# triple_filter.net
KiCad netlist of a schematic drawn in EAGLE
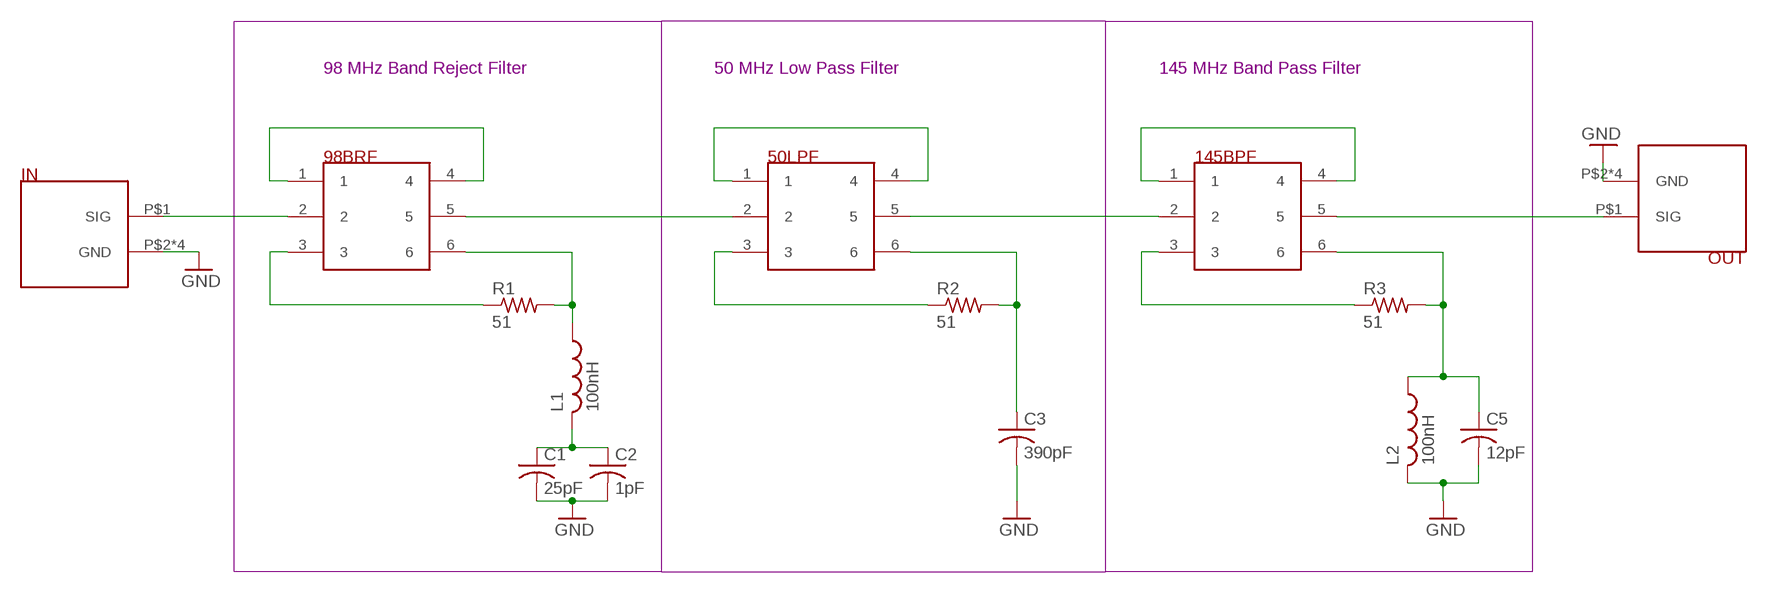
[diagram p0: schematic, sheet 1]

(export (version "E")
  (design (tool "Eeschema 10.0.6"))
  (components
    (comp (ref "50LPF")
      (value "JS202011SCQN")
      (footprint "eagle-import:JS202011SCQN")
      (libsource (lib "eagle-import") (part "JS202011SCQN"))
    )
    (comp (ref "98BRF")
      (value "JS202011SCQN")
      (footprint "eagle-import:JS202011SCQN")
      (libsource (lib "eagle-import") (part "JS202011SCQN"))
    )
    (comp (ref "145BPF")
      (value "JS202011SCQN")
      (footprint "eagle-import:JS202011SCQN")
      (libsource (lib "eagle-import") (part "JS202011SCQN"))
    )
    (comp (ref "C1")
      (value "25pF")
      (footprint "eagle-import:C0805")
      (libsource (lib "eagle-import") (part "C-USC0805"))
    )
    (comp (ref "C2")
      (value "1pF")
      (footprint "eagle-import:C0805")
      (libsource (lib "eagle-import") (part "C-USC0805"))
    )
    (comp (ref "C3")
      (value "390pF")
      (footprint "eagle-import:C0805")
      (libsource (lib "eagle-import") (part "C-USC0805"))
    )
    (comp (ref "C5")
      (value "12pF")
      (footprint "eagle-import:C0805")
      (libsource (lib "eagle-import") (part "C-USC0805"))
    )
    (comp (ref "IN")
      (value "SMA-CONN")
      (footprint "eagle-import:SMA-CONN")
      (libsource (lib "eagle-import") (part "SMA-CONN"))
    )
    (comp (ref "L1")
      (value "100nH")
      (footprint "eagle-import:L2012C")
      (libsource (lib "eagle-import") (part "L-USL2012C"))
    )
    (comp (ref "L2")
      (value "100nH")
      (footprint "eagle-import:L2012C")
      (libsource (lib "eagle-import") (part "L-USL2012C"))
    )
    (comp (ref "OUT")
      (value "SMA-CONN")
      (footprint "eagle-import:SMA-CONN")
      (libsource (lib "eagle-import") (part "SMA-CONN"))
    )
    (comp (ref "R1")
      (value "51")
      (footprint "eagle-import:R0805")
      (libsource (lib "eagle-import") (part "R-US_R0805"))
    )
    (comp (ref "R2")
      (value "51")
      (footprint "eagle-import:R0805")
      (libsource (lib "eagle-import") (part "R-US_R0805"))
    )
    (comp (ref "R3")
      (value "51")
      (footprint "eagle-import:R0805")
      (libsource (lib "eagle-import") (part "R-US_R0805"))
    )
  )
  (nets
    (net (code "1") (name "GND") (class "Default")
      (node (ref "C1") (pin "2") (pinfunction "2_2") (pintype "passive"))
      (node (ref "C2") (pin "2") (pinfunction "2_2") (pintype "passive"))
      (node (ref "C3") (pin "2") (pinfunction "2_2") (pintype "passive"))
      (node (ref "C5") (pin "2") (pinfunction "2_2") (pintype "passive"))
      (node (ref "IN") (pin "P$2") (pinfunction "GND_P$2") (pintype "bidirectional"))
      (node (ref "IN") (pin "P$3") (pinfunction "GND_P$3") (pintype "bidirectional"))
      (node (ref "IN") (pin "P$4") (pinfunction "GND_P$4") (pintype "bidirectional"))
      (node (ref "IN") (pin "P$5") (pinfunction "GND_P$5") (pintype "bidirectional"))
      (node (ref "L2") (pin "2") (pinfunction "2_2") (pintype "passive"))
      (node (ref "OUT") (pin "P$2") (pinfunction "GND_P$2") (pintype "bidirectional"))
      (node (ref "OUT") (pin "P$3") (pinfunction "GND_P$3") (pintype "bidirectional"))
      (node (ref "OUT") (pin "P$4") (pinfunction "GND_P$4") (pintype "bidirectional"))
      (node (ref "OUT") (pin "P$5") (pinfunction "GND_P$5") (pintype "bidirectional"))
    )
    (net (code "2") (name "Net-(50LPF-Pad1)") (class "Default")
      (node (ref "50LPF") (pin "1") (pinfunction "1_1") (pintype "bidirectional"))
      (node (ref "50LPF") (pin "4") (pinfunction "4_4") (pintype "bidirectional"))
    )
    (net (code "3") (name "Net-(50LPF-Pad2)") (class "Default")
      (node (ref "50LPF") (pin "2") (pinfunction "2_2") (pintype "bidirectional"))
      (node (ref "98BRF") (pin "5") (pinfunction "5_5") (pintype "bidirectional"))
    )
    (net (code "4") (name "Net-(50LPF-Pad3)") (class "Default")
      (node (ref "50LPF") (pin "3") (pinfunction "3_3") (pintype "bidirectional"))
      (node (ref "R2") (pin "1") (pinfunction "1_1") (pintype "passive"))
    )
    (net (code "5") (name "Net-(50LPF-Pad6)") (class "Default")
      (node (ref "50LPF") (pin "6") (pinfunction "6_6") (pintype "bidirectional"))
      (node (ref "C3") (pin "1") (pinfunction "1_1") (pintype "passive"))
      (node (ref "R2") (pin "2") (pinfunction "2_2") (pintype "passive"))
    )
    (net (code "6") (name "Net-(98BRF-Pad1)") (class "Default")
      (node (ref "98BRF") (pin "1") (pinfunction "1_1") (pintype "bidirectional"))
      (node (ref "98BRF") (pin "4") (pinfunction "4_4") (pintype "bidirectional"))
    )
    (net (code "7") (name "Net-(98BRF-Pad3)") (class "Default")
      (node (ref "98BRF") (pin "3") (pinfunction "3_3") (pintype "bidirectional"))
      (node (ref "R1") (pin "1") (pinfunction "1_1") (pintype "passive"))
    )
    (net (code "8") (name "Net-(98BRF-Pad6)") (class "Default")
      (node (ref "98BRF") (pin "6") (pinfunction "6_6") (pintype "bidirectional"))
      (node (ref "L1") (pin "1") (pinfunction "1_1") (pintype "passive"))
      (node (ref "R1") (pin "2") (pinfunction "2_2") (pintype "passive"))
    )
    (net (code "9") (name "Net-(145BPF-Pad1)") (class "Default")
      (node (ref "145BPF") (pin "1") (pinfunction "1_1") (pintype "bidirectional"))
      (node (ref "145BPF") (pin "4") (pinfunction "4_4") (pintype "bidirectional"))
    )
    (net (code "10") (name "Net-(145BPF-Pad2)") (class "Default")
      (node (ref "145BPF") (pin "2") (pinfunction "2_2") (pintype "bidirectional"))
      (node (ref "50LPF") (pin "5") (pinfunction "5_5") (pintype "bidirectional"))
    )
    (net (code "11") (name "Net-(145BPF-Pad3)") (class "Default")
      (node (ref "145BPF") (pin "3") (pinfunction "3_3") (pintype "bidirectional"))
      (node (ref "R3") (pin "1") (pinfunction "1_1") (pintype "passive"))
    )
    (net (code "12") (name "Net-(145BPF-Pad6)") (class "Default")
      (node (ref "145BPF") (pin "6") (pinfunction "6_6") (pintype "bidirectional"))
      (node (ref "C5") (pin "1") (pinfunction "1_1") (pintype "passive"))
      (node (ref "L2") (pin "1") (pinfunction "1_1") (pintype "passive"))
      (node (ref "R3") (pin "2") (pinfunction "2_2") (pintype "passive"))
    )
    (net (code "13") (name "Net-(C1-Pad1)") (class "Default")
      (node (ref "C1") (pin "1") (pinfunction "1_1") (pintype "passive"))
      (node (ref "C2") (pin "1") (pinfunction "1_1") (pintype "passive"))
      (node (ref "L1") (pin "2") (pinfunction "2_2") (pintype "passive"))
    )
    (net (code "14") (name "Net-(IN-SIG)") (class "Default")
      (node (ref "98BRF") (pin "2") (pinfunction "2_2") (pintype "bidirectional"))
      (node (ref "IN") (pin "P$1") (pinfunction "SIG_P$1") (pintype "bidirectional"))
    )
    (net (code "15") (name "Net-(OUT-SIG)") (class "Default")
      (node (ref "145BPF") (pin "5") (pinfunction "5_5") (pintype "bidirectional"))
      (node (ref "OUT") (pin "P$1") (pinfunction "SIG_P$1") (pintype "bidirectional"))
    )
  )
)
